# SDP_1.net
KiCad netlist of a schematic drawn in Altium Designer
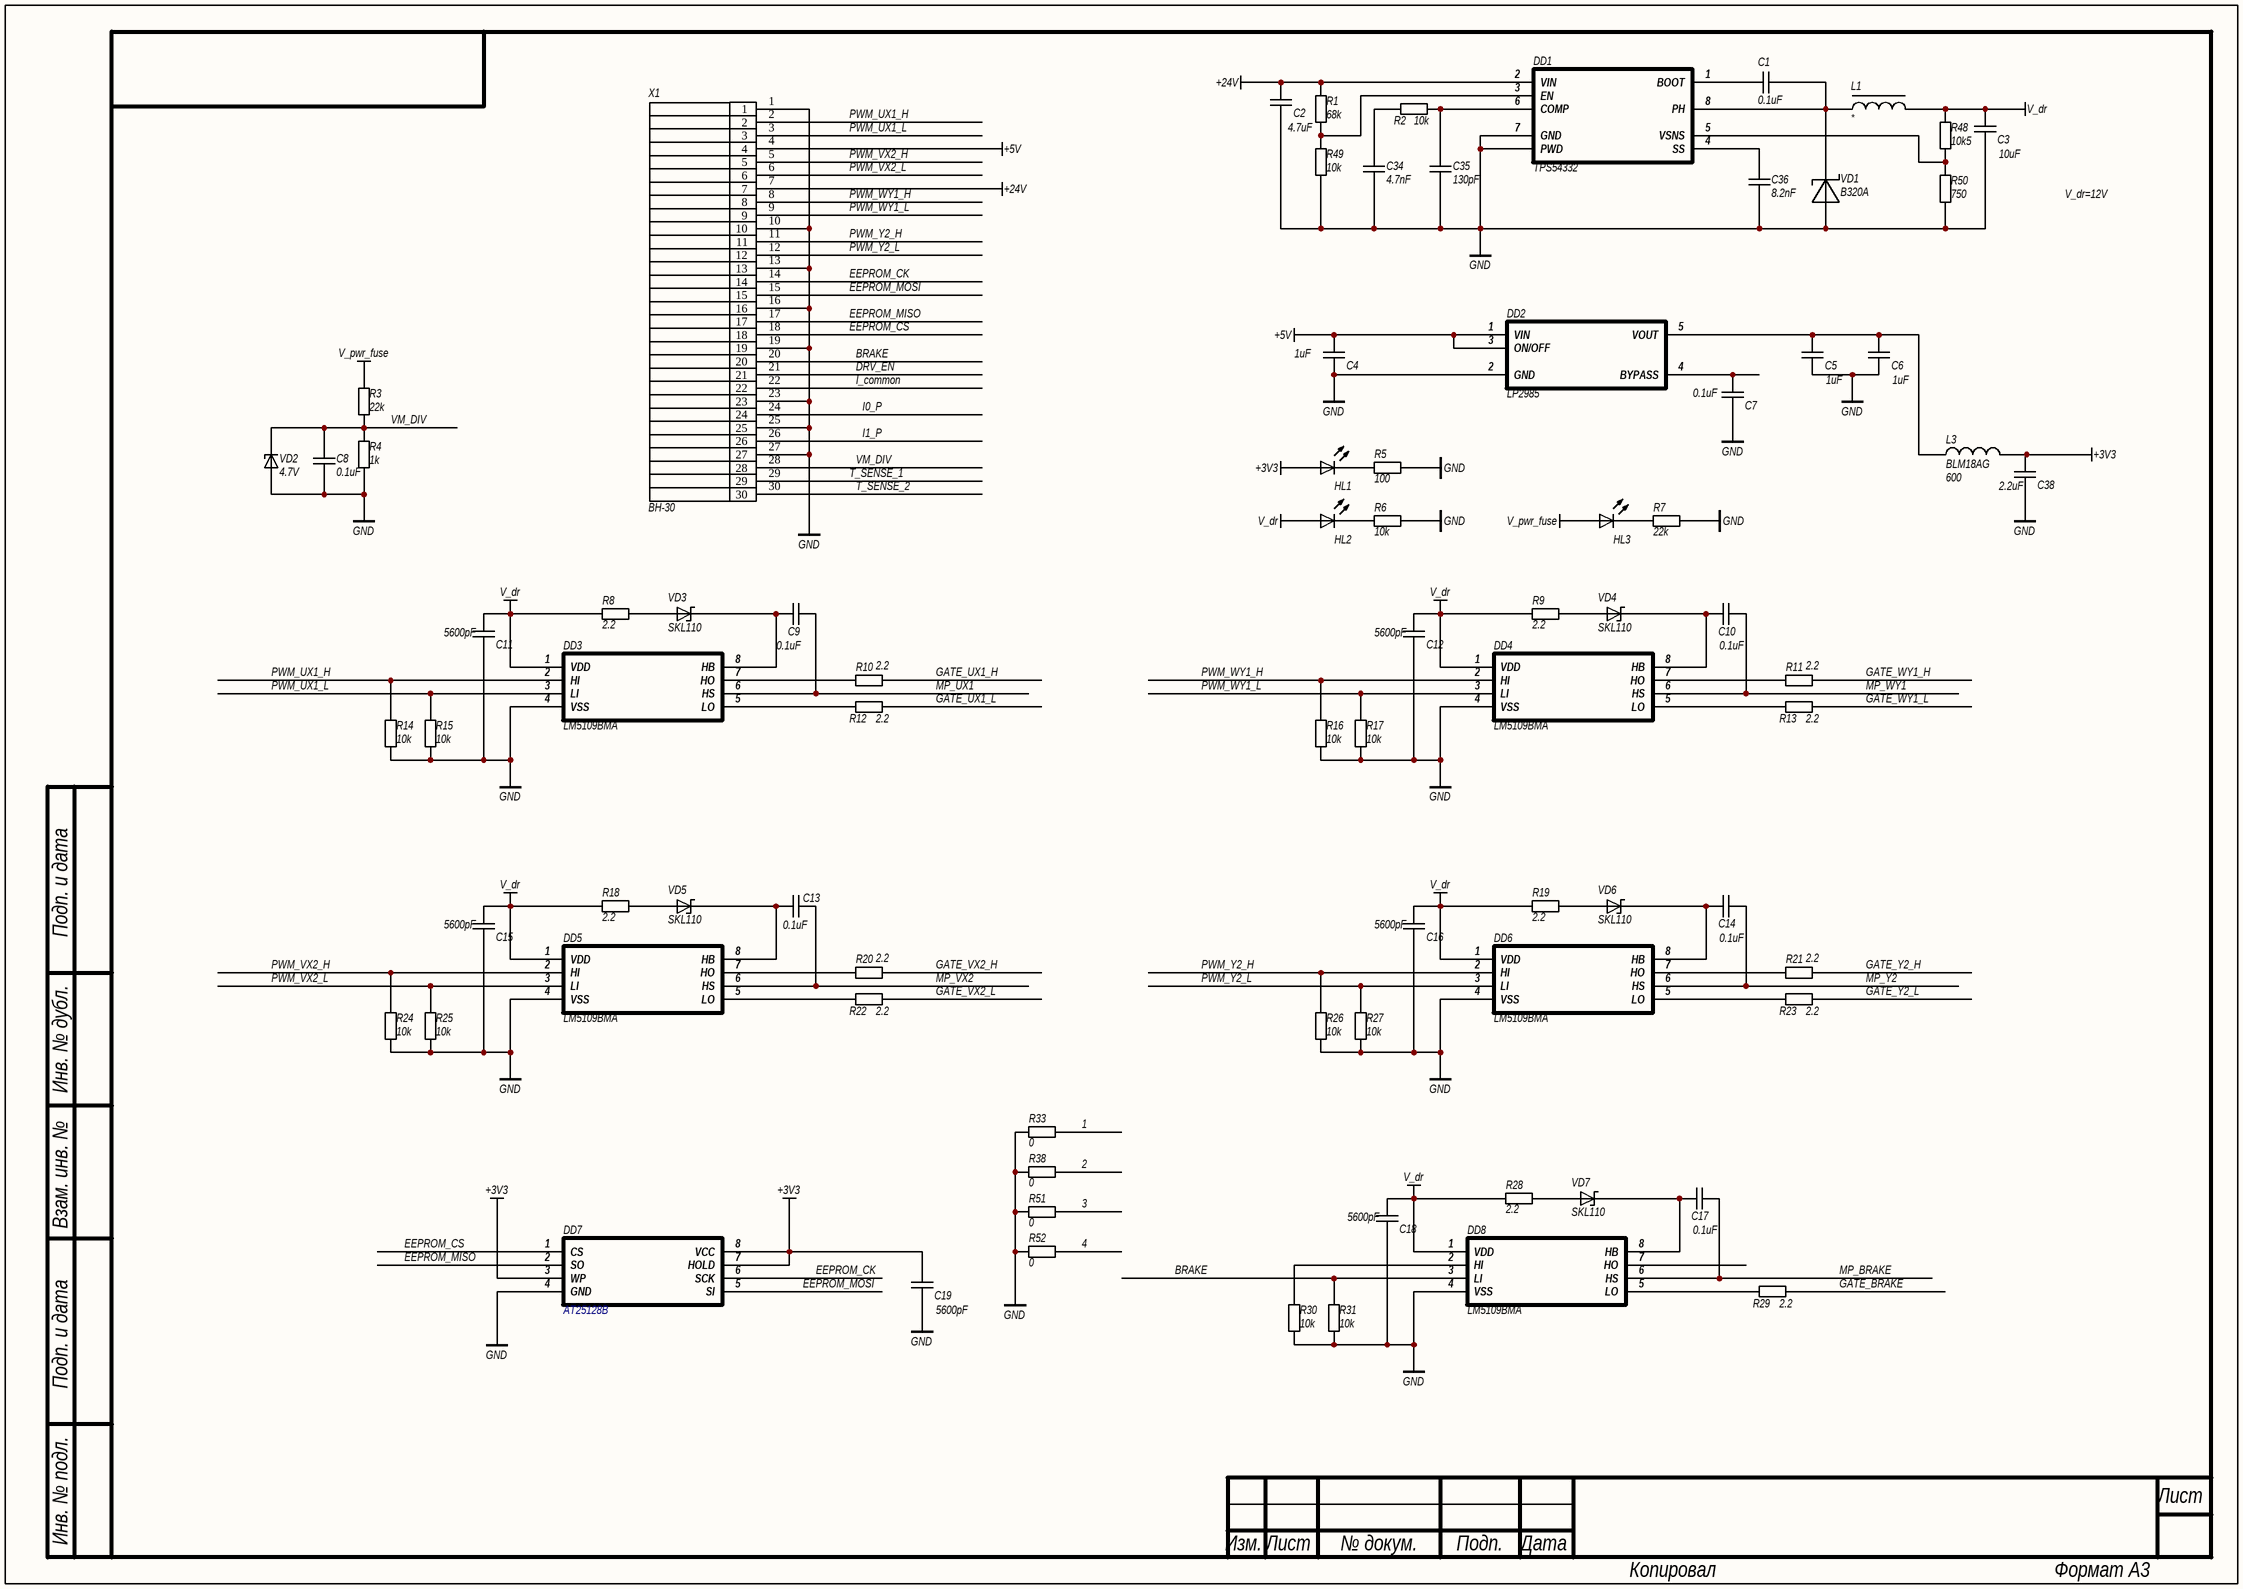
[diagram p0: SDP_1.SchDoc]

(export (version "E")
  (design (tool "Eeschema 10.0.6"))
  (components
    (comp (ref "C1")
      (value "0.1uF")
      (footprint "C0603")
      (description "SMD Capacitor")
      (fields (field (name "MANUFACTURER") "Murata") (field (name "TOLERANCE") "10%"))
      (libsource (lib "VKA") (part "CAP"))
    )
    (comp (ref "C2")
      (value "4.7uF")
      (footprint "C1210")
      (description "SMD Capacitor")
      (fields (field (name "MANUFACTURER") "Murata") (field (name "TOLERANCE") "10%"))
      (libsource (lib "VKA") (part "CAP"))
    )
    (comp (ref "C3")
      (value "10uF")
      (footprint "C1210")
      (description "SMD Capacitor")
      (fields (field (name "MANUFACTURER") "Murata") (field (name "TOLERANCE") "10%"))
      (libsource (lib "VKA") (part "CAP"))
    )
    (comp (ref "C4")
      (value "1uF")
      (footprint "C0603")
      (description "SMD Capacitor")
      (fields (field (name "MANUFACTURER") "Murata") (field (name "TOLERANCE") "10%"))
      (libsource (lib "VKA") (part "CAP"))
    )
    (comp (ref "C5")
      (value "1uF")
      (footprint "C0603")
      (description "SMD Capacitor")
      (fields (field (name "MANUFACTURER") "Murata") (field (name "TOLERANCE") "10%"))
      (libsource (lib "VKA") (part "CAP"))
    )
    (comp (ref "C6")
      (value "1uF")
      (footprint "C0603")
      (description "SMD Capacitor")
      (fields (field (name "MANUFACTURER") "Murata") (field (name "TOLERANCE") "10%"))
      (libsource (lib "VKA") (part "CAP"))
    )
    (comp (ref "C7")
      (value "0.1uF")
      (footprint "C0603")
      (description "SMD Capacitor")
      (fields (field (name "MANUFACTURER") "Murata") (field (name "TOLERANCE") "10%"))
      (libsource (lib "VKA") (part "CAP"))
    )
    (comp (ref "C8")
      (value "0.1uF")
      (footprint "C0603")
      (description "SMD Capacitor")
      (fields (field (name "MANUFACTURER") "Murata") (field (name "TOLERANCE") "10%"))
      (libsource (lib "VKA") (part "CAP"))
    )
    (comp (ref "C9")
      (value "0.1uF")
      (footprint "C0603")
      (description "SMD Capacitor")
      (fields (field (name "MANUFACTURER") "Murata") (field (name "TOLERANCE") "10%"))
      (libsource (lib "VKA") (part "CAP"))
    )
    (comp (ref "C10")
      (value "0.1uF")
      (footprint "C0603")
      (description "SMD Capacitor")
      (fields (field (name "MANUFACTURER") "Murata") (field (name "TOLERANCE") "10%"))
      (libsource (lib "VKA") (part "CAP"))
    )
    (comp (ref "C11")
      (value "5600pF")
      (footprint "C0603")
      (description "SMD Capacitor")
      (fields (field (name "MANUFACTURER") "Murata") (field (name "TOLERANCE") "10%"))
      (libsource (lib "VKA") (part "CAP"))
    )
    (comp (ref "C12")
      (value "5600pF")
      (footprint "C0603")
      (description "SMD Capacitor")
      (fields (field (name "MANUFACTURER") "Murata") (field (name "TOLERANCE") "10%"))
      (libsource (lib "VKA") (part "CAP"))
    )
    (comp (ref "C13")
      (value "0.1uF")
      (footprint "C0603")
      (description "SMD Capacitor")
      (fields (field (name "MANUFACTURER") "Murata") (field (name "TOLERANCE") "10%"))
      (libsource (lib "VKA") (part "CAP"))
    )
    (comp (ref "C14")
      (value "0.1uF")
      (footprint "C0603")
      (description "SMD Capacitor")
      (fields (field (name "MANUFACTURER") "Murata") (field (name "TOLERANCE") "10%"))
      (libsource (lib "VKA") (part "CAP"))
    )
    (comp (ref "C15")
      (value "5600pF")
      (footprint "C0603")
      (description "SMD Capacitor")
      (fields (field (name "MANUFACTURER") "Murata") (field (name "TOLERANCE") "10%"))
      (libsource (lib "VKA") (part "CAP"))
    )
    (comp (ref "C16")
      (value "5600pF")
      (footprint "C0603")
      (description "SMD Capacitor")
      (fields (field (name "MANUFACTURER") "Murata") (field (name "TOLERANCE") "10%"))
      (libsource (lib "VKA") (part "CAP"))
    )
    (comp (ref "C17")
      (value "0.1uF")
      (footprint "C0603")
      (description "SMD Capacitor")
      (fields (field (name "MANUFACTURER") "Murata") (field (name "TOLERANCE") "10%"))
      (libsource (lib "VKA") (part "CAP"))
    )
    (comp (ref "C18")
      (value "5600pF")
      (footprint "C0603")
      (description "SMD Capacitor")
      (fields (field (name "MANUFACTURER") "Murata") (field (name "TOLERANCE") "10%"))
      (libsource (lib "VKA") (part "CAP"))
    )
    (comp (ref "C19")
      (value "5600pF")
      (footprint "C0603")
      (description "SMD Capacitor")
      (fields (field (name "MANUFACTURER") "Murata") (field (name "TOLERANCE") "10%"))
      (libsource (lib "VKA") (part "CAP"))
    )
    (comp (ref "C34")
      (value "4.7nF")
      (footprint "C0603")
      (description "SMD Capacitor")
      (fields (field (name "MANUFACTURER") "Murata") (field (name "TOLERANCE") "10%"))
      (libsource (lib "VKA") (part "CAP"))
    )
    (comp (ref "C35")
      (value "130pF")
      (footprint "C0603")
      (description "SMD Capacitor")
      (fields (field (name "MANUFACTURER") "Murata") (field (name "TOLERANCE") "10%"))
      (libsource (lib "VKA") (part "CAP"))
    )
    (comp (ref "C36")
      (value "8.2nF")
      (footprint "C0603")
      (description "SMD Capacitor")
      (fields (field (name "MANUFACTURER") "Murata") (field (name "TOLERANCE") "10%"))
      (libsource (lib "VKA") (part "CAP"))
    )
    (comp (ref "C38")
      (value "2.2uF")
      (footprint "C0603")
      (description "SMD Capacitor")
      (fields (field (name "MANUFACTURER") "Murata") (field (name "TOLERANCE") "10%"))
      (libsource (lib "VKA") (part "CAP"))
    )
    (comp (ref "DD1") (value "TPS54332") (footprint "DDA") (libsource (lib "VKA") (part "TPS54332")))
    (comp (ref "DD2")
      (value "LP2985")
      (footprint "SOT23-5")
      (description "Regulator")
      (libsource (lib "DSP") (part "LP2985-33DBV"))
    )
    (comp (ref "DD3")
      (value "LM5109BMA")
      (footprint "SO8_L")
      (description "Gate driver")
      (libsource (lib "DSP") (part "LM5109BMA"))
    )
    (comp (ref "DD4")
      (value "LM5109BMA")
      (footprint "SO8_L")
      (description "Gate driver")
      (libsource (lib "DSP") (part "LM5109BMA"))
    )
    (comp (ref "DD5")
      (value "LM5109BMA")
      (footprint "SO8_L")
      (description "Gate driver")
      (libsource (lib "DSP") (part "LM5109BMA"))
    )
    (comp (ref "DD6")
      (value "LM5109BMA")
      (footprint "SO8_L")
      (description "Gate driver")
      (libsource (lib "DSP") (part "LM5109BMA"))
    )
    (comp (ref "DD7")
      (value "AT25128B")
      (footprint "SO8_L")
      (description "EEPROM")
      (libsource (lib "DSP") (part "AT25128B-SSHL"))
    )
    (comp (ref "DD8")
      (value "LM5109BMA")
      (footprint "SO8_L")
      (description "Gate driver")
      (libsource (lib "DSP") (part "LM5109BMA"))
    )
    (comp (ref "HL1") (value "LED0603") (footprint "LED0603") (libsource (lib "VKA") (part "LED0603")))
    (comp (ref "HL2") (value "LED0603") (footprint "LED0603") (libsource (lib "VKA") (part "LED0603")))
    (comp (ref "HL3") (value "LED0603") (footprint "LED0603") (libsource (lib "VKA") (part "LED0603")))
    (comp (ref "L1")
      (value "XAL5050")
      (footprint "XAL5050")
      (description "chip inductor")
      (fields (field (name "ALTIUM_VALUE") "*"))
      (libsource (lib "VKA") (part "XAL5050"))
    )
    (comp (ref "L3")
      (value "BLM18AG")
      (footprint "R0603")
      (fields (field (name "ALTIUM_VALUE") "600"))
      (libsource (lib "VKA") (part "BLM18AG"))
    )
    (comp (ref "R1")
      (value "68k")
      (footprint "R0603")
      (description "SMD Resistor")
      (fields (field (name "POWER") "0.062 Wt") (field (name "TOLERANCE") "5%"))
      (libsource (lib "VKA") (part "RES"))
    )
    (comp (ref "R2")
      (value "10k")
      (footprint "R0603")
      (description "SMD Resistor")
      (fields (field (name "POWER") "0.062 Wt") (field (name "TOLERANCE") "5%"))
      (libsource (lib "") (part "RES_2"))
    )
    (comp (ref "R3")
      (value "22k")
      (footprint "R0603")
      (description "SMD Resistor")
      (fields (field (name "POWER") "0.062 Wt") (field (name "TOLERANCE") "5%"))
      (libsource (lib "VKA") (part "RES"))
    )
    (comp (ref "R4")
      (value "1k")
      (footprint "R0603")
      (description "SMD Resistor")
      (fields (field (name "POWER") "0.062 Wt") (field (name "TOLERANCE") "5%"))
      (libsource (lib "VKA") (part "RES"))
    )
    (comp (ref "R5")
      (value "100")
      (footprint "R0603")
      (description "SMD Resistor")
      (fields (field (name "POWER") "0.062 Wt") (field (name "TOLERANCE") "5%"))
      (libsource (lib "") (part "RES_2"))
    )
    (comp (ref "R6")
      (value "10k")
      (footprint "R0603")
      (description "SMD Resistor")
      (fields (field (name "POWER") "0.062 Wt") (field (name "TOLERANCE") "5%"))
      (libsource (lib "") (part "RES_2"))
    )
    (comp (ref "R7")
      (value "22k")
      (footprint "R0603")
      (description "SMD Resistor")
      (fields (field (name "POWER") "0.062 Wt") (field (name "TOLERANCE") "5%"))
      (libsource (lib "") (part "RES_2"))
    )
    (comp (ref "R8")
      (value "2.2")
      (footprint "R0603")
      (description "SMD Resistor")
      (fields (field (name "POWER") "0.062 Wt") (field (name "TOLERANCE") "5%"))
      (libsource (lib "") (part "RES_1"))
    )
    (comp (ref "R9")
      (value "2.2")
      (footprint "R0603")
      (description "SMD Resistor")
      (fields (field (name "POWER") "0.062 Wt") (field (name "TOLERANCE") "5%"))
      (libsource (lib "") (part "RES_1"))
    )
    (comp (ref "R10")
      (value "2.2")
      (footprint "R0603")
      (description "SMD Resistor")
      (fields (field (name "POWER") "0.062 Wt") (field (name "TOLERANCE") "5%"))
      (libsource (lib "") (part "RES_1"))
    )
    (comp (ref "R11")
      (value "2.2")
      (footprint "R0603")
      (description "SMD Resistor")
      (fields (field (name "POWER") "0.062 Wt") (field (name "TOLERANCE") "5%"))
      (libsource (lib "") (part "RES_1"))
    )
    (comp (ref "R12")
      (value "2.2")
      (footprint "R0603")
      (description "SMD Resistor")
      (fields (field (name "POWER") "0.062 Wt") (field (name "TOLERANCE") "5%"))
      (libsource (lib "") (part "RES_1"))
    )
    (comp (ref "R13")
      (value "2.2")
      (footprint "R0603")
      (description "SMD Resistor")
      (fields (field (name "POWER") "0.062 Wt") (field (name "TOLERANCE") "5%"))
      (libsource (lib "") (part "RES_1"))
    )
    (comp (ref "R14")
      (value "10k")
      (footprint "R0603")
      (description "SMD Resistor")
      (fields (field (name "POWER") "0.062 Wt") (field (name "TOLERANCE") "5%"))
      (libsource (lib "VKA") (part "RES"))
    )
    (comp (ref "R15")
      (value "10k")
      (footprint "R0603")
      (description "SMD Resistor")
      (fields (field (name "POWER") "0.062 Wt") (field (name "TOLERANCE") "5%"))
      (libsource (lib "VKA") (part "RES"))
    )
    (comp (ref "R16")
      (value "10k")
      (footprint "R0603")
      (description "SMD Resistor")
      (fields (field (name "POWER") "0.062 Wt") (field (name "TOLERANCE") "5%"))
      (libsource (lib "VKA") (part "RES"))
    )
    (comp (ref "R17")
      (value "10k")
      (footprint "R0603")
      (description "SMD Resistor")
      (fields (field (name "POWER") "0.062 Wt") (field (name "TOLERANCE") "5%"))
      (libsource (lib "VKA") (part "RES"))
    )
    (comp (ref "R18")
      (value "2.2")
      (footprint "R0603")
      (description "SMD Resistor")
      (fields (field (name "POWER") "0.062 Wt") (field (name "TOLERANCE") "5%"))
      (libsource (lib "") (part "RES_1"))
    )
    (comp (ref "R19")
      (value "2.2")
      (footprint "R0603")
      (description "SMD Resistor")
      (fields (field (name "POWER") "0.062 Wt") (field (name "TOLERANCE") "5%"))
      (libsource (lib "") (part "RES_1"))
    )
    (comp (ref "R20")
      (value "2.2")
      (footprint "R0603")
      (description "SMD Resistor")
      (fields (field (name "POWER") "0.062 Wt") (field (name "TOLERANCE") "5%"))
      (libsource (lib "") (part "RES_1"))
    )
    (comp (ref "R21")
      (value "2.2")
      (footprint "R0603")
      (description "SMD Resistor")
      (fields (field (name "POWER") "0.062 Wt") (field (name "TOLERANCE") "5%"))
      (libsource (lib "") (part "RES_1"))
    )
    (comp (ref "R22")
      (value "2.2")
      (footprint "R0603")
      (description "SMD Resistor")
      (fields (field (name "POWER") "0.062 Wt") (field (name "TOLERANCE") "5%"))
      (libsource (lib "") (part "RES_1"))
    )
    (comp (ref "R23")
      (value "2.2")
      (footprint "R0603")
      (description "SMD Resistor")
      (fields (field (name "POWER") "0.062 Wt") (field (name "TOLERANCE") "5%"))
      (libsource (lib "") (part "RES_1"))
    )
    (comp (ref "R24")
      (value "10k")
      (footprint "R0603")
      (description "SMD Resistor")
      (fields (field (name "POWER") "0.062 Wt") (field (name "TOLERANCE") "5%"))
      (libsource (lib "VKA") (part "RES"))
    )
    (comp (ref "R25")
      (value "10k")
      (footprint "R0603")
      (description "SMD Resistor")
      (fields (field (name "POWER") "0.062 Wt") (field (name "TOLERANCE") "5%"))
      (libsource (lib "VKA") (part "RES"))
    )
    (comp (ref "R26")
      (value "10k")
      (footprint "R0603")
      (description "SMD Resistor")
      (fields (field (name "POWER") "0.062 Wt") (field (name "TOLERANCE") "5%"))
      (libsource (lib "VKA") (part "RES"))
    )
    (comp (ref "R27")
      (value "10k")
      (footprint "R0603")
      (description "SMD Resistor")
      (fields (field (name "POWER") "0.062 Wt") (field (name "TOLERANCE") "5%"))
      (libsource (lib "VKA") (part "RES"))
    )
    (comp (ref "R28")
      (value "2.2")
      (footprint "R0603")
      (description "SMD Resistor")
      (fields (field (name "POWER") "0.062 Wt") (field (name "TOLERANCE") "5%"))
      (libsource (lib "") (part "RES_1"))
    )
    (comp (ref "R29")
      (value "2.2")
      (footprint "R0603")
      (description "SMD Resistor")
      (fields (field (name "POWER") "0.062 Wt") (field (name "TOLERANCE") "5%"))
      (libsource (lib "") (part "RES_1"))
    )
    (comp (ref "R30")
      (value "10k")
      (footprint "R0603")
      (description "SMD Resistor")
      (fields (field (name "POWER") "0.062 Wt") (field (name "TOLERANCE") "5%"))
      (libsource (lib "VKA") (part "RES"))
    )
    (comp (ref "R31")
      (value "10k")
      (footprint "R0603")
      (description "SMD Resistor")
      (fields (field (name "POWER") "0.062 Wt") (field (name "TOLERANCE") "5%"))
      (libsource (lib "VKA") (part "RES"))
    )
    (comp (ref "R33")
      (value "0")
      (footprint "R0603")
      (description "SMD Resistor")
      (fields (field (name "POWER") "0.062 Wt") (field (name "TOLERANCE") "5%"))
      (libsource (lib "") (part "RES_2"))
    )
    (comp (ref "R38")
      (value "0")
      (footprint "R0603")
      (description "SMD Resistor")
      (fields (field (name "POWER") "0.062 Wt") (field (name "TOLERANCE") "5%"))
      (libsource (lib "") (part "RES_2"))
    )
    (comp (ref "R48")
      (value "10k5")
      (footprint "R0603")
      (description "SMD Resistor")
      (fields (field (name "POWER") "0.062 Wt") (field (name "TOLERANCE") "5%"))
      (libsource (lib "VKA") (part "RES"))
    )
    (comp (ref "R49")
      (value "10k")
      (footprint "R0603")
      (description "SMD Resistor")
      (fields (field (name "POWER") "0.062 Wt") (field (name "TOLERANCE") "5%"))
      (libsource (lib "VKA") (part "RES"))
    )
    (comp (ref "R50")
      (value "750")
      (footprint "R0603")
      (description "SMD Resistor")
      (fields (field (name "POWER") "0.062 Wt") (field (name "TOLERANCE") "5%"))
      (libsource (lib "VKA") (part "RES"))
    )
    (comp (ref "R51")
      (value "0")
      (footprint "R0603")
      (description "SMD Resistor")
      (fields (field (name "POWER") "0.062 Wt") (field (name "TOLERANCE") "5%"))
      (libsource (lib "") (part "RES_2"))
    )
    (comp (ref "R52")
      (value "0")
      (footprint "R0603")
      (description "SMD Resistor")
      (fields (field (name "POWER") "0.062 Wt") (field (name "TOLERANCE") "5%"))
      (libsource (lib "") (part "RES_2"))
    )
    (comp (ref "VD1")
      (value "B320A")
      (footprint "SMA-DO214")
      (description "Shottky diode")
      (libsource (lib "VKA") (part "B320A"))
    )
    (comp (ref "VD2")
      (value "BZX384")
      (footprint "SOD323")
      (fields (field (name "VOLTAGE") "4.7V"))
      (libsource (lib "VKA") (part "BZX384"))
    )
    (comp (ref "VD3")
      (value "SKL110")
      (footprint "SOD-123")
      (description "Shottky rectifier")
      (libsource (lib "DSP") (part "SKL110"))
    )
    (comp (ref "VD4")
      (value "SKL110")
      (footprint "SOD-123")
      (description "Shottky rectifier")
      (libsource (lib "DSP") (part "SKL110"))
    )
    (comp (ref "VD5")
      (value "SKL110")
      (footprint "SOD-123")
      (description "Shottky rectifier")
      (libsource (lib "DSP") (part "SKL110"))
    )
    (comp (ref "VD6")
      (value "SKL110")
      (footprint "SOD-123")
      (description "Shottky rectifier")
      (libsource (lib "DSP") (part "SKL110"))
    )
    (comp (ref "VD7")
      (value "SKL110")
      (footprint "SOD-123")
      (description "Shottky rectifier")
      (libsource (lib "DSP") (part "SKL110"))
    )
    (comp (ref "X1")
      (value "BH-30")
      (footprint "IDC-30(BH-30)")
      (libsource (lib "VKA") (part "IDC15x2_GOST"))
    )
  )
  (nets
    (net (code "1") (name "+3V3") (class "Default")
      (node (ref "C19") (pin "2") (pinfunction "2_2") (pintype "passive"))
      (node (ref "C38") (pin "2") (pinfunction "2_2") (pintype "passive"))
      (node (ref "DD7") (pin "3") (pinfunction "WP_3") (pintype "passive"))
      (node (ref "DD7") (pin "7") (pinfunction "HOLD_7") (pintype "passive"))
      (node (ref "DD7") (pin "8") (pinfunction "VCC_8") (pintype "passive"))
      (node (ref "HL1") (pin "1") (pinfunction "A_1") (pintype "passive"))
      (node (ref "L3") (pin "2") (pinfunction "2_2") (pintype "passive"))
    )
    (net (code "2") (name "+5V") (class "Default")
      (node (ref "C4") (pin "2") (pinfunction "2_2") (pintype "passive"))
      (node (ref "DD2") (pin "1") (pinfunction "VIN_1") (pintype "passive"))
      (node (ref "DD2") (pin "3") (pinfunction "ON/OFF_3") (pintype "passive"))
      (node (ref "X1") (pin "4") (pinfunction "4_4") (pintype "passive"))
    )
    (net (code "3") (name "+24V") (class "Default")
      (node (ref "C2") (pin "2") (pinfunction "2_2") (pintype "passive"))
      (node (ref "DD1") (pin "2") (pinfunction "VIN_2") (pintype "passive"))
      (node (ref "R1") (pin "2") (pinfunction "2_2") (pintype "passive"))
      (node (ref "X1") (pin "7") (pinfunction "7_7") (pintype "passive"))
    )
    (net (code "4") (name "/1") (class "Default")
      (node (ref "R33") (pin "1") (pinfunction "1_1") (pintype "passive"))
    )
    (net (code "5") (name "/2") (class "Default")
      (node (ref "R38") (pin "1") (pinfunction "1_1") (pintype "passive"))
    )
    (net (code "6") (name "/3") (class "Default")
      (node (ref "R51") (pin "1") (pinfunction "1_1") (pintype "passive"))
    )
    (net (code "7") (name "/4") (class "Default")
      (node (ref "R52") (pin "1") (pinfunction "1_1") (pintype "passive"))
    )
    (net (code "8") (name "/BRAKE") (class "Default")
      (node (ref "DD8") (pin "3") (pinfunction "LI_3") (pintype "passive"))
      (node (ref "R31") (pin "2") (pinfunction "2_2") (pintype "passive"))
      (node (ref "X1") (pin "20") (pinfunction "20_20") (pintype "passive"))
    )
    (net (code "9") (name "/DRV_EN") (class "Default")
      (node (ref "X1") (pin "21") (pinfunction "21_21") (pintype "passive"))
    )
    (net (code "10") (name "/EEPROM_CK") (class "Default")
      (node (ref "DD7") (pin "6") (pinfunction "SCK_6") (pintype "passive"))
      (node (ref "X1") (pin "14") (pinfunction "14_14") (pintype "passive"))
    )
    (net (code "11") (name "/EEPROM_CS") (class "Default")
      (node (ref "DD7") (pin "1") (pinfunction "CS_1") (pintype "passive"))
      (node (ref "X1") (pin "18") (pinfunction "18_18") (pintype "passive"))
    )
    (net (code "12") (name "/EEPROM_MISO") (class "Default")
      (node (ref "DD7") (pin "2") (pinfunction "SO_2") (pintype "passive"))
      (node (ref "X1") (pin "17") (pinfunction "17_17") (pintype "passive"))
    )
    (net (code "13") (name "/EEPROM_MOSI") (class "Default")
      (node (ref "DD7") (pin "5") (pinfunction "SI_5") (pintype "passive"))
      (node (ref "X1") (pin "15") (pinfunction "15_15") (pintype "passive"))
    )
    (net (code "14") (name "/GATE_BRAKE") (class "Default")
      (node (ref "R29") (pin "2") (pinfunction "2_2") (pintype "passive"))
    )
    (net (code "15") (name "/GATE_UX1_H") (class "Default")
      (node (ref "R10") (pin "2") (pinfunction "2_2") (pintype "passive"))
    )
    (net (code "16") (name "/GATE_UX1_L") (class "Default")
      (node (ref "R12") (pin "2") (pinfunction "2_2") (pintype "passive"))
    )
    (net (code "17") (name "/GATE_VX2_H") (class "Default")
      (node (ref "R20") (pin "2") (pinfunction "2_2") (pintype "passive"))
    )
    (net (code "18") (name "/GATE_VX2_L") (class "Default")
      (node (ref "R22") (pin "2") (pinfunction "2_2") (pintype "passive"))
    )
    (net (code "19") (name "/GATE_WY1_H") (class "Default")
      (node (ref "R11") (pin "2") (pinfunction "2_2") (pintype "passive"))
    )
    (net (code "20") (name "/GATE_WY1_L") (class "Default")
      (node (ref "R13") (pin "2") (pinfunction "2_2") (pintype "passive"))
    )
    (net (code "21") (name "/GATE_Y2_H") (class "Default")
      (node (ref "R21") (pin "2") (pinfunction "2_2") (pintype "passive"))
    )
    (net (code "22") (name "/GATE_Y2_L") (class "Default")
      (node (ref "R23") (pin "2") (pinfunction "2_2") (pintype "passive"))
    )
    (net (code "23") (name "/I0_P") (class "Default")
      (node (ref "X1") (pin "24") (pinfunction "24_24") (pintype "passive"))
    )
    (net (code "24") (name "/I1_P") (class "Default")
      (node (ref "X1") (pin "26") (pinfunction "26_26") (pintype "passive"))
    )
    (net (code "25") (name "/I_common") (class "Default")
      (node (ref "X1") (pin "22") (pinfunction "22_22") (pintype "passive"))
    )
    (net (code "26") (name "/MP_BRAKE") (class "Default")
      (node (ref "C17") (pin "2") (pinfunction "2_2") (pintype "passive"))
      (node (ref "DD8") (pin "6") (pinfunction "HS_6") (pintype "passive"))
    )
    (net (code "27") (name "/MP_UX1") (class "Default")
      (node (ref "C9") (pin "2") (pinfunction "2_2") (pintype "passive"))
      (node (ref "DD3") (pin "6") (pinfunction "HS_6") (pintype "passive"))
    )
    (net (code "28") (name "/MP_VX2") (class "Default")
      (node (ref "C13") (pin "2") (pinfunction "2_2") (pintype "passive"))
      (node (ref "DD5") (pin "6") (pinfunction "HS_6") (pintype "passive"))
    )
    (net (code "29") (name "/MP_WY1") (class "Default")
      (node (ref "C10") (pin "2") (pinfunction "2_2") (pintype "passive"))
      (node (ref "DD4") (pin "6") (pinfunction "HS_6") (pintype "passive"))
    )
    (net (code "30") (name "/MP_Y2") (class "Default")
      (node (ref "C14") (pin "2") (pinfunction "2_2") (pintype "passive"))
      (node (ref "DD6") (pin "6") (pinfunction "HS_6") (pintype "passive"))
    )
    (net (code "31") (name "/PWM_UX1_H") (class "Default")
      (node (ref "DD3") (pin "2") (pinfunction "HI_2") (pintype "passive"))
      (node (ref "R14") (pin "2") (pinfunction "2_2") (pintype "passive"))
      (node (ref "X1") (pin "2") (pinfunction "2_2") (pintype "passive"))
    )
    (net (code "32") (name "/PWM_UX1_L") (class "Default")
      (node (ref "DD3") (pin "3") (pinfunction "LI_3") (pintype "passive"))
      (node (ref "R15") (pin "2") (pinfunction "2_2") (pintype "passive"))
      (node (ref "X1") (pin "3") (pinfunction "3_3") (pintype "passive"))
    )
    (net (code "33") (name "/PWM_VX2_H") (class "Default")
      (node (ref "DD5") (pin "2") (pinfunction "HI_2") (pintype "passive"))
      (node (ref "R24") (pin "2") (pinfunction "2_2") (pintype "passive"))
      (node (ref "X1") (pin "5") (pinfunction "5_5") (pintype "passive"))
    )
    (net (code "34") (name "/PWM_VX2_L") (class "Default")
      (node (ref "DD5") (pin "3") (pinfunction "LI_3") (pintype "passive"))
      (node (ref "R25") (pin "2") (pinfunction "2_2") (pintype "passive"))
      (node (ref "X1") (pin "6") (pinfunction "6_6") (pintype "passive"))
    )
    (net (code "35") (name "/PWM_WY1_H") (class "Default")
      (node (ref "DD4") (pin "2") (pinfunction "HI_2") (pintype "passive"))
      (node (ref "R16") (pin "2") (pinfunction "2_2") (pintype "passive"))
      (node (ref "X1") (pin "8") (pinfunction "8_8") (pintype "passive"))
    )
    (net (code "36") (name "/PWM_WY1_L") (class "Default")
      (node (ref "DD4") (pin "3") (pinfunction "LI_3") (pintype "passive"))
      (node (ref "R17") (pin "2") (pinfunction "2_2") (pintype "passive"))
      (node (ref "X1") (pin "9") (pinfunction "9_9") (pintype "passive"))
    )
    (net (code "37") (name "/PWM_Y2_H") (class "Default")
      (node (ref "DD6") (pin "2") (pinfunction "HI_2") (pintype "passive"))
      (node (ref "R26") (pin "2") (pinfunction "2_2") (pintype "passive"))
      (node (ref "X1") (pin "11") (pinfunction "11_11") (pintype "passive"))
    )
    (net (code "38") (name "/PWM_Y2_L") (class "Default")
      (node (ref "DD6") (pin "3") (pinfunction "LI_3") (pintype "passive"))
      (node (ref "R27") (pin "2") (pinfunction "2_2") (pintype "passive"))
      (node (ref "X1") (pin "12") (pinfunction "12_12") (pintype "passive"))
    )
    (net (code "39") (name "/T_SENSE_1") (class "Default")
      (node (ref "X1") (pin "29") (pinfunction "29_29") (pintype "passive"))
    )
    (net (code "40") (name "/T_SENSE_2") (class "Default")
      (node (ref "X1") (pin "30") (pinfunction "30_30") (pintype "passive"))
    )
    (net (code "41") (name "/VM_DIV") (class "Default")
      (node (ref "C8") (pin "2") (pinfunction "2_2") (pintype "passive"))
      (node (ref "R3") (pin "1") (pinfunction "1_1") (pintype "passive"))
      (node (ref "R4") (pin "2") (pinfunction "2_2") (pintype "passive"))
      (node (ref "VD2") (pin "2") (pinfunction "K_2") (pintype "passive"))
      (node (ref "X1") (pin "28") (pinfunction "28_28") (pintype "passive"))
    )
    (net (code "42") (name "GND") (class "Default")
      (node (ref "C11") (pin "1") (pinfunction "1_1") (pintype "passive"))
      (node (ref "C12") (pin "1") (pinfunction "1_1") (pintype "passive"))
      (node (ref "C15") (pin "1") (pinfunction "1_1") (pintype "passive"))
      (node (ref "C16") (pin "1") (pinfunction "1_1") (pintype "passive"))
      (node (ref "C18") (pin "1") (pinfunction "1_1") (pintype "passive"))
      (node (ref "C19") (pin "1") (pinfunction "1_1") (pintype "passive"))
      (node (ref "C2") (pin "1") (pinfunction "1_1") (pintype "passive"))
      (node (ref "C3") (pin "1") (pinfunction "1_1") (pintype "passive"))
      (node (ref "C34") (pin "1") (pinfunction "1_1") (pintype "passive"))
      (node (ref "C35") (pin "1") (pinfunction "1_1") (pintype "passive"))
      (node (ref "C36") (pin "1") (pinfunction "1_1") (pintype "passive"))
      (node (ref "C38") (pin "1") (pinfunction "1_1") (pintype "passive"))
      (node (ref "C4") (pin "1") (pinfunction "1_1") (pintype "passive"))
      (node (ref "C5") (pin "1") (pinfunction "1_1") (pintype "passive"))
      (node (ref "C6") (pin "1") (pinfunction "1_1") (pintype "passive"))
      (node (ref "C7") (pin "1") (pinfunction "1_1") (pintype "passive"))
      (node (ref "C8") (pin "1") (pinfunction "1_1") (pintype "passive"))
      (node (ref "DD1") (pin "7") (pinfunction "GND_7") (pintype "passive"))
      (node (ref "DD1") (pin "9") (pinfunction "PWD_9") (pintype "passive"))
      (node (ref "DD2") (pin "2") (pinfunction "GND_2") (pintype "passive"))
      (node (ref "DD3") (pin "4") (pinfunction "VSS_4") (pintype "passive"))
      (node (ref "DD4") (pin "4") (pinfunction "VSS_4") (pintype "passive"))
      (node (ref "DD5") (pin "4") (pinfunction "VSS_4") (pintype "passive"))
      (node (ref "DD6") (pin "4") (pinfunction "VSS_4") (pintype "passive"))
      (node (ref "DD7") (pin "4") (pinfunction "GND_4") (pintype "passive"))
      (node (ref "DD8") (pin "4") (pinfunction "VSS_4") (pintype "passive"))
      (node (ref "R14") (pin "1") (pinfunction "1_1") (pintype "passive"))
      (node (ref "R15") (pin "1") (pinfunction "1_1") (pintype "passive"))
      (node (ref "R16") (pin "1") (pinfunction "1_1") (pintype "passive"))
      (node (ref "R17") (pin "1") (pinfunction "1_1") (pintype "passive"))
      (node (ref "R24") (pin "1") (pinfunction "1_1") (pintype "passive"))
      (node (ref "R25") (pin "1") (pinfunction "1_1") (pintype "passive"))
      (node (ref "R26") (pin "1") (pinfunction "1_1") (pintype "passive"))
      (node (ref "R27") (pin "1") (pinfunction "1_1") (pintype "passive"))
      (node (ref "R30") (pin "1") (pinfunction "1_1") (pintype "passive"))
      (node (ref "R31") (pin "1") (pinfunction "1_1") (pintype "passive"))
      (node (ref "R33") (pin "2") (pinfunction "2_2") (pintype "passive"))
      (node (ref "R38") (pin "2") (pinfunction "2_2") (pintype "passive"))
      (node (ref "R4") (pin "1") (pinfunction "1_1") (pintype "passive"))
      (node (ref "R49") (pin "1") (pinfunction "1_1") (pintype "passive"))
      (node (ref "R5") (pin "1") (pinfunction "1_1") (pintype "passive"))
      (node (ref "R50") (pin "1") (pinfunction "1_1") (pintype "passive"))
      (node (ref "R51") (pin "2") (pinfunction "2_2") (pintype "passive"))
      (node (ref "R52") (pin "2") (pinfunction "2_2") (pintype "passive"))
      (node (ref "R6") (pin "1") (pinfunction "1_1") (pintype "passive"))
      (node (ref "R7") (pin "1") (pinfunction "1_1") (pintype "passive"))
      (node (ref "VD1") (pin "1") (pinfunction "A_1") (pintype "passive"))
      (node (ref "VD2") (pin "1") (pinfunction "A_1") (pintype "passive"))
      (node (ref "X1") (pin "1") (pinfunction "1_1") (pintype "passive"))
      (node (ref "X1") (pin "10") (pinfunction "10_10") (pintype "passive"))
      (node (ref "X1") (pin "13") (pinfunction "13_13") (pintype "passive"))
      (node (ref "X1") (pin "16") (pinfunction "16_16") (pintype "passive"))
      (node (ref "X1") (pin "19") (pinfunction "19_19") (pintype "passive"))
      (node (ref "X1") (pin "23") (pinfunction "23_23") (pintype "passive"))
      (node (ref "X1") (pin "25") (pinfunction "25_25") (pintype "passive"))
      (node (ref "X1") (pin "27") (pinfunction "27_27") (pintype "passive"))
    )
    (net (code "43") (name "Net-(C34-Pad2)") (class "Default")
      (node (ref "C34") (pin "2") (pinfunction "2_2") (pintype "passive"))
      (node (ref "R2") (pin "2") (pinfunction "2_2") (pintype "passive"))
    )
    (net (code "44") (name "Net-(DD1-BOOT)") (class "Default")
      (node (ref "C1") (pin "2") (pinfunction "2_2") (pintype "passive"))
      (node (ref "DD1") (pin "1") (pinfunction "BOOT_1") (pintype "passive"))
    )
    (net (code "45") (name "Net-(DD1-COMP)") (class "Default")
      (node (ref "C35") (pin "2") (pinfunction "2_2") (pintype "passive"))
      (node (ref "DD1") (pin "6") (pinfunction "COMP_6") (pintype "passive"))
      (node (ref "R2") (pin "1") (pinfunction "1_1") (pintype "passive"))
    )
    (net (code "46") (name "Net-(DD1-EN)") (class "Default")
      (node (ref "DD1") (pin "3") (pinfunction "EN_3") (pintype "passive"))
      (node (ref "R1") (pin "1") (pinfunction "1_1") (pintype "passive"))
      (node (ref "R49") (pin "2") (pinfunction "2_2") (pintype "passive"))
    )
    (net (code "47") (name "Net-(DD1-PH)") (class "Default")
      (node (ref "C1") (pin "1") (pinfunction "1_1") (pintype "passive"))
      (node (ref "DD1") (pin "8") (pinfunction "PH_8") (pintype "passive"))
      (node (ref "L1") (pin "1") (pinfunction "1_1") (pintype "passive"))
      (node (ref "VD1") (pin "2") (pinfunction "K_2") (pintype "passive"))
    )
    (net (code "48") (name "Net-(DD1-SS)") (class "Default")
      (node (ref "C36") (pin "2") (pinfunction "2_2") (pintype "passive"))
      (node (ref "DD1") (pin "4") (pinfunction "SS_4") (pintype "passive"))
    )
    (net (code "49") (name "Net-(DD1-VSNS)") (class "Default")
      (node (ref "DD1") (pin "5") (pinfunction "VSNS_5") (pintype "passive"))
      (node (ref "R48") (pin "1") (pinfunction "1_1") (pintype "passive"))
      (node (ref "R50") (pin "2") (pinfunction "2_2") (pintype "passive"))
    )
    (net (code "50") (name "Net-(DD2-BYPASS)") (class "Default")
      (node (ref "C7") (pin "2") (pinfunction "2_2") (pintype "passive"))
      (node (ref "DD2") (pin "4") (pinfunction "BYPASS_4") (pintype "passive"))
    )
    (net (code "51") (name "Net-(DD2-VOUT)") (class "Default")
      (node (ref "C5") (pin "2") (pinfunction "2_2") (pintype "passive"))
      (node (ref "C6") (pin "2") (pinfunction "2_2") (pintype "passive"))
      (node (ref "DD2") (pin "5") (pinfunction "VOUT_5") (pintype "passive"))
      (node (ref "L3") (pin "1") (pinfunction "1_1") (pintype "passive"))
    )
    (net (code "52") (name "Net-(DD3-HB)") (class "Default")
      (node (ref "C9") (pin "1") (pinfunction "1_1") (pintype "passive"))
      (node (ref "DD3") (pin "8") (pinfunction "HB_8") (pintype "passive"))
      (node (ref "VD3") (pin "2") (pinfunction "K_2") (pintype "passive"))
    )
    (net (code "53") (name "Net-(DD3-HO)") (class "Default")
      (node (ref "DD3") (pin "7") (pinfunction "HO_7") (pintype "passive"))
      (node (ref "R10") (pin "1") (pinfunction "1_1") (pintype "passive"))
    )
    (net (code "54") (name "Net-(DD3-LO)") (class "Default")
      (node (ref "DD3") (pin "5") (pinfunction "LO_5") (pintype "passive"))
      (node (ref "R12") (pin "1") (pinfunction "1_1") (pintype "passive"))
    )
    (net (code "55") (name "Net-(DD4-HB)") (class "Default")
      (node (ref "C10") (pin "1") (pinfunction "1_1") (pintype "passive"))
      (node (ref "DD4") (pin "8") (pinfunction "HB_8") (pintype "passive"))
      (node (ref "VD4") (pin "2") (pinfunction "K_2") (pintype "passive"))
    )
    (net (code "56") (name "Net-(DD4-HO)") (class "Default")
      (node (ref "DD4") (pin "7") (pinfunction "HO_7") (pintype "passive"))
      (node (ref "R11") (pin "1") (pinfunction "1_1") (pintype "passive"))
    )
    (net (code "57") (name "Net-(DD4-LO)") (class "Default")
      (node (ref "DD4") (pin "5") (pinfunction "LO_5") (pintype "passive"))
      (node (ref "R13") (pin "1") (pinfunction "1_1") (pintype "passive"))
    )
    (net (code "58") (name "Net-(DD5-HB)") (class "Default")
      (node (ref "C13") (pin "1") (pinfunction "1_1") (pintype "passive"))
      (node (ref "DD5") (pin "8") (pinfunction "HB_8") (pintype "passive"))
      (node (ref "VD5") (pin "2") (pinfunction "K_2") (pintype "passive"))
    )
    (net (code "59") (name "Net-(DD5-HO)") (class "Default")
      (node (ref "DD5") (pin "7") (pinfunction "HO_7") (pintype "passive"))
      (node (ref "R20") (pin "1") (pinfunction "1_1") (pintype "passive"))
    )
    (net (code "60") (name "Net-(DD5-LO)") (class "Default")
      (node (ref "DD5") (pin "5") (pinfunction "LO_5") (pintype "passive"))
      (node (ref "R22") (pin "1") (pinfunction "1_1") (pintype "passive"))
    )
    (net (code "61") (name "Net-(DD6-HB)") (class "Default")
      (node (ref "C14") (pin "1") (pinfunction "1_1") (pintype "passive"))
      (node (ref "DD6") (pin "8") (pinfunction "HB_8") (pintype "passive"))
      (node (ref "VD6") (pin "2") (pinfunction "K_2") (pintype "passive"))
    )
    (net (code "62") (name "Net-(DD6-HO)") (class "Default")
      (node (ref "DD6") (pin "7") (pinfunction "HO_7") (pintype "passive"))
      (node (ref "R21") (pin "1") (pinfunction "1_1") (pintype "passive"))
    )
    (net (code "63") (name "Net-(DD6-LO)") (class "Default")
      (node (ref "DD6") (pin "5") (pinfunction "LO_5") (pintype "passive"))
      (node (ref "R23") (pin "1") (pinfunction "1_1") (pintype "passive"))
    )
    (net (code "64") (name "Net-(DD8-HB)") (class "Default")
      (node (ref "C17") (pin "1") (pinfunction "1_1") (pintype "passive"))
      (node (ref "DD8") (pin "8") (pinfunction "HB_8") (pintype "passive"))
      (node (ref "VD7") (pin "2") (pinfunction "K_2") (pintype "passive"))
    )
    (net (code "65") (name "Net-(DD8-HI)") (class "Default")
      (node (ref "DD8") (pin "2") (pinfunction "HI_2") (pintype "passive"))
      (node (ref "R30") (pin "2") (pinfunction "2_2") (pintype "passive"))
    )
    (net (code "66") (name "Net-(DD8-LO)") (class "Default")
      (node (ref "DD8") (pin "5") (pinfunction "LO_5") (pintype "passive"))
      (node (ref "R29") (pin "1") (pinfunction "1_1") (pintype "passive"))
    )
    (net (code "67") (name "Net-(HL1-K)") (class "Default")
      (node (ref "HL1") (pin "2") (pinfunction "K_2") (pintype "passive"))
      (node (ref "R5") (pin "2") (pinfunction "2_2") (pintype "passive"))
    )
    (net (code "68") (name "Net-(HL2-K)") (class "Default")
      (node (ref "HL2") (pin "2") (pinfunction "K_2") (pintype "passive"))
      (node (ref "R6") (pin "2") (pinfunction "2_2") (pintype "passive"))
    )
    (net (code "69") (name "Net-(HL3-K)") (class "Default")
      (node (ref "HL3") (pin "2") (pinfunction "K_2") (pintype "passive"))
      (node (ref "R7") (pin "2") (pinfunction "2_2") (pintype "passive"))
    )
    (net (code "70") (name "Net-(VD3-A)") (class "Default")
      (node (ref "R8") (pin "2") (pinfunction "2_2") (pintype "passive"))
      (node (ref "VD3") (pin "1") (pinfunction "A_1") (pintype "passive"))
    )
    (net (code "71") (name "Net-(VD4-A)") (class "Default")
      (node (ref "R9") (pin "2") (pinfunction "2_2") (pintype "passive"))
      (node (ref "VD4") (pin "1") (pinfunction "A_1") (pintype "passive"))
    )
    (net (code "72") (name "Net-(VD5-A)") (class "Default")
      (node (ref "R18") (pin "2") (pinfunction "2_2") (pintype "passive"))
      (node (ref "VD5") (pin "1") (pinfunction "A_1") (pintype "passive"))
    )
    (net (code "73") (name "Net-(VD6-A)") (class "Default")
      (node (ref "R19") (pin "2") (pinfunction "2_2") (pintype "passive"))
      (node (ref "VD6") (pin "1") (pinfunction "A_1") (pintype "passive"))
    )
    (net (code "74") (name "Net-(VD7-A)") (class "Default")
      (node (ref "R28") (pin "2") (pinfunction "2_2") (pintype "passive"))
      (node (ref "VD7") (pin "1") (pinfunction "A_1") (pintype "passive"))
    )
    (net (code "75") (name "V_dr") (class "Default")
      (node (ref "C11") (pin "2") (pinfunction "2_2") (pintype "passive"))
      (node (ref "C12") (pin "2") (pinfunction "2_2") (pintype "passive"))
      (node (ref "C15") (pin "2") (pinfunction "2_2") (pintype "passive"))
      (node (ref "C16") (pin "2") (pinfunction "2_2") (pintype "passive"))
      (node (ref "C18") (pin "2") (pinfunction "2_2") (pintype "passive"))
      (node (ref "C3") (pin "2") (pinfunction "2_2") (pintype "passive"))
      (node (ref "DD3") (pin "1") (pinfunction "VDD_1") (pintype "passive"))
      (node (ref "DD4") (pin "1") (pinfunction "VDD_1") (pintype "passive"))
      (node (ref "DD5") (pin "1") (pinfunction "VDD_1") (pintype "passive"))
      (node (ref "DD6") (pin "1") (pinfunction "VDD_1") (pintype "passive"))
      (node (ref "DD8") (pin "1") (pinfunction "VDD_1") (pintype "passive"))
      (node (ref "HL2") (pin "1") (pinfunction "A_1") (pintype "passive"))
      (node (ref "L1") (pin "2") (pinfunction "2_2") (pintype "passive"))
      (node (ref "R18") (pin "1") (pinfunction "1_1") (pintype "passive"))
      (node (ref "R19") (pin "1") (pinfunction "1_1") (pintype "passive"))
      (node (ref "R28") (pin "1") (pinfunction "1_1") (pintype "passive"))
      (node (ref "R48") (pin "2") (pinfunction "2_2") (pintype "passive"))
      (node (ref "R8") (pin "1") (pinfunction "1_1") (pintype "passive"))
      (node (ref "R9") (pin "1") (pinfunction "1_1") (pintype "passive"))
    )
    (net (code "76") (name "V_pwr_fuse") (class "Default")
      (node (ref "HL3") (pin "1") (pinfunction "A_1") (pintype "passive"))
      (node (ref "R3") (pin "2") (pinfunction "2_2") (pintype "passive"))
    )
    (net (code "77") (name "unconnected-(DD8-HO-Pad7)") (class "Default")
      (node (ref "DD8") (pin "7") (pinfunction "HO_7") (pintype "passive"))
    )
  )
)
